# arm.net
KiCad netlist of a schematic drawn in Altium Designer
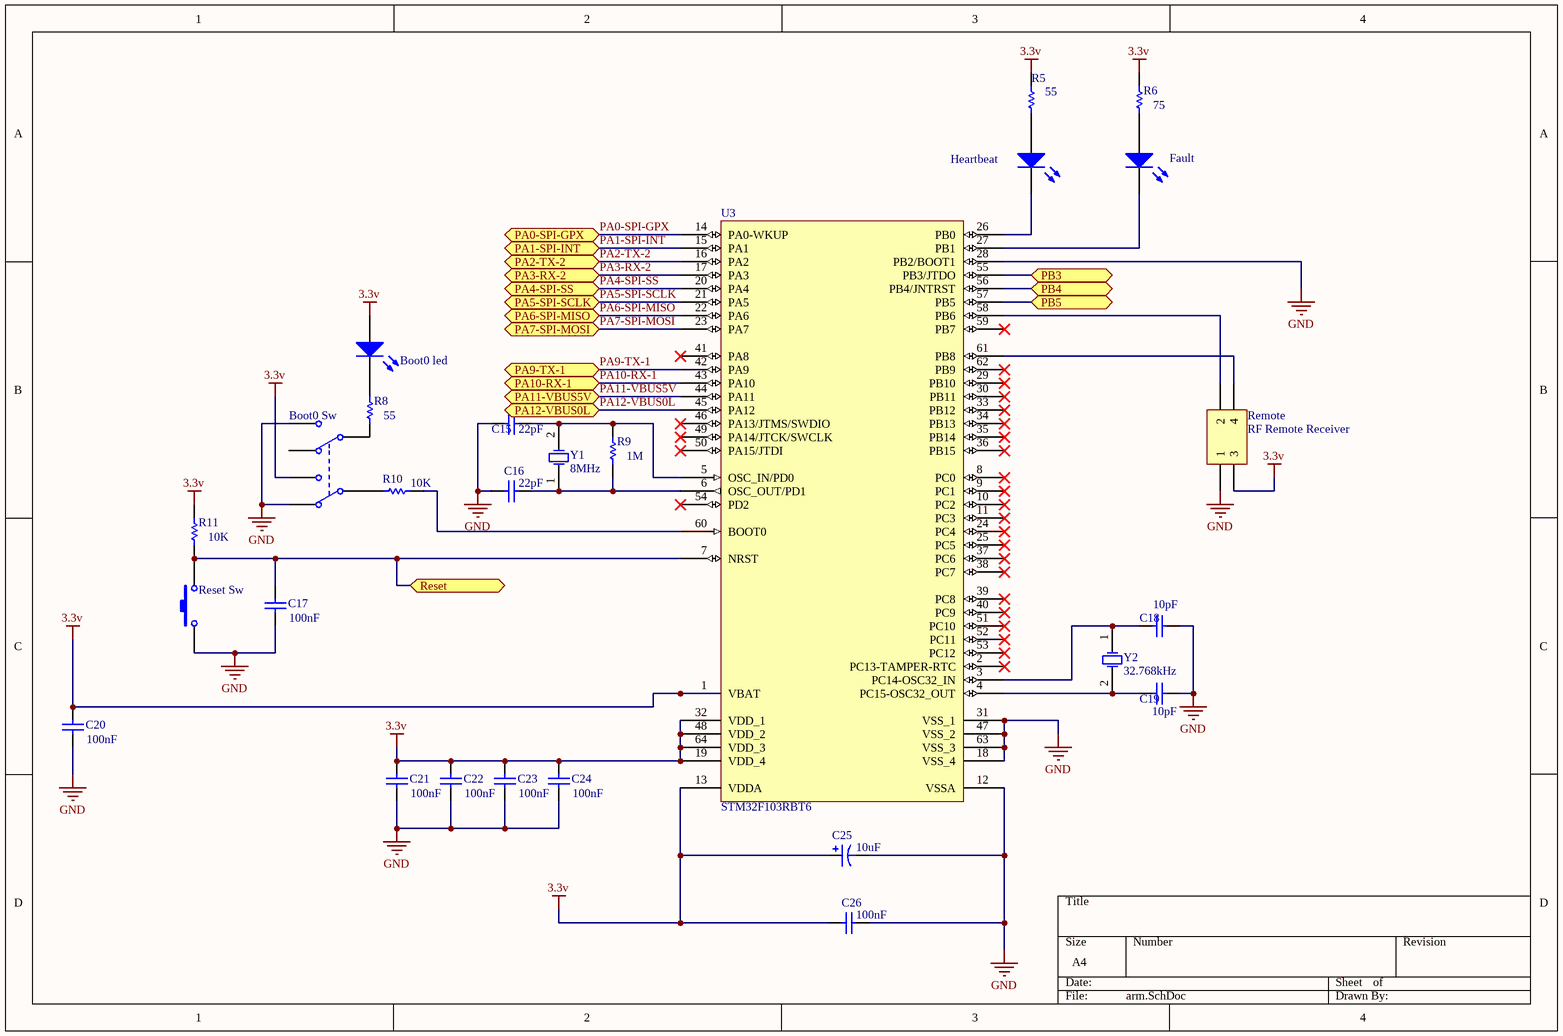
[diagram p0: arm.SchDoc]

(export (version "E")
  (design (tool "Eeschema 10.0.6"))
  (components
    (comp (ref "Boot0")
      (value "Boot0 led")
      (footprint "3.2X1.6X1.1")
      (description "Typical RED, GREEN, YELLOW, AMBER GaAs LED")
      (fields (field (name "PUBLISHER") "Altium Limited"))
      (libsource (lib "Miscellaneous Devices") (part "LED2"))
    )
    (comp (ref "Boot0 Sw")
      (value "BOOT0 SW")
      (footprint "Switch DPDT")
      (description "Switch")
      (fields (field (name "PUBLISHER") "Altium Limited"))
      (libsource (lib "Miscellaneous Devices") (part "SW DPDT"))
    )
    (comp (ref "C15")
      (value "22pF")
      (footprint "CAPC1608L")
      (description "Capacitor")
      (fields (field (name "Comment") "Cap") (field (name "PUBLISHER") "Altium Limited"))
      (libsource (lib "Miscellaneous Devices") (part "Cap"))
    )
    (comp (ref "C16")
      (value "22pF")
      (footprint "CAPC1608L")
      (description "Capacitor")
      (fields (field (name "Comment") "Cap") (field (name "PUBLISHER") "Altium Limited"))
      (libsource (lib "Miscellaneous Devices") (part "Cap"))
    )
    (comp (ref "C17")
      (value "100nF")
      (footprint "CAPC1608L")
      (description "Capacitor")
      (fields (field (name "Comment") "Cap") (field (name "PUBLISHER") "Altium Limited"))
      (libsource (lib "Miscellaneous Devices") (part "Cap"))
    )
    (comp (ref "C18")
      (value "10pF")
      (footprint "CAPC1608L")
      (description "Capacitor")
      (fields (field (name "Comment") "Cap") (field (name "PUBLISHER") "Altium Limited"))
      (libsource (lib "Miscellaneous Devices") (part "Cap"))
    )
    (comp (ref "C19")
      (value "10pF")
      (footprint "CAPC1608L")
      (description "Capacitor")
      (fields (field (name "Comment") "Cap") (field (name "PUBLISHER") "Altium Limited"))
      (libsource (lib "Miscellaneous Devices") (part "Cap"))
    )
    (comp (ref "C20")
      (value "100nF")
      (footprint "CAPC1608L")
      (description "Capacitor")
      (fields (field (name "Comment") "Cap") (field (name "PUBLISHER") "Altium Limited"))
      (libsource (lib "Miscellaneous Devices") (part "Cap"))
    )
    (comp (ref "C21")
      (value "100nF")
      (footprint "CAPC1608L")
      (description "Capacitor")
      (fields (field (name "Comment") "Cap") (field (name "PUBLISHER") "Altium Limited"))
      (libsource (lib "Miscellaneous Devices") (part "Cap"))
    )
    (comp (ref "C22")
      (value "100nF")
      (footprint "CAPC1608L")
      (description "Capacitor")
      (fields (field (name "Comment") "Cap") (field (name "PUBLISHER") "Altium Limited"))
      (libsource (lib "Miscellaneous Devices") (part "Cap"))
    )
    (comp (ref "C23")
      (value "100nF")
      (footprint "CAPC1608L")
      (description "Capacitor")
      (fields (field (name "Comment") "Cap") (field (name "PUBLISHER") "Altium Limited"))
      (libsource (lib "Miscellaneous Devices") (part "Cap"))
    )
    (comp (ref "C24")
      (value "100nF")
      (footprint "CAPC1608L")
      (description "Capacitor")
      (fields (field (name "Comment") "Cap") (field (name "PUBLISHER") "Altium Limited"))
      (libsource (lib "Miscellaneous Devices") (part "Cap"))
    )
    (comp (ref "C25")
      (value "10uF")
      (footprint "CAPC3216M")
      (description "Polarized Capacitor (Surface Mount)")
      (fields (field (name "Comment") "Cap Pol3") (field (name "PUBLISHER") "Altium Limited"))
      (libsource (lib "Miscellaneous Devices") (part "Cap Pol3"))
    )
    (comp (ref "C26")
      (value "100nF")
      (footprint "CAPC1608L")
      (description "Capacitor")
      (fields (field (name "Comment") "Cap") (field (name "PUBLISHER") "Altium Limited"))
      (libsource (lib "Miscellaneous Devices") (part "Cap"))
    )
    (comp (ref "Fault")
      (value "Fault LED")
      (footprint "3.2X1.6X1.1")
      (description "Typical RED, GREEN, YELLOW, AMBER GaAs LED")
      (fields (field (name "PUBLISHER") "Altium Limited"))
      (libsource (lib "Miscellaneous Devices") (part "LED2"))
    )
    (comp (ref "Heartbeat")
      (value "Heartbeat LED")
      (footprint "3.2X1.6X1.1")
      (description "Typical RED, GREEN, YELLOW, AMBER GaAs LED")
      (fields (field (name "PUBLISHER") "Altium Limited"))
      (libsource (lib "Miscellaneous Devices") (part "LED2"))
    )
    (comp (ref "R5")
      (value "55")
      (footprint "RESC1608L")
      (description "Resistor")
      (fields (field (name "Comment") "Res1") (field (name "PUBLISHER") "Altium Limited"))
      (libsource (lib "Miscellaneous Devices") (part "Res1"))
    )
    (comp (ref "R6")
      (value "75")
      (footprint "RESC1608L")
      (description "Resistor")
      (fields (field (name "Comment") "Res1") (field (name "PUBLISHER") "Altium Limited"))
      (libsource (lib "Miscellaneous Devices") (part "Res1"))
    )
    (comp (ref "R8")
      (value "55")
      (footprint "RESC1608L")
      (description "Resistor")
      (fields (field (name "Comment") "Res1") (field (name "PUBLISHER") "Altium Limited"))
      (libsource (lib "Miscellaneous Devices") (part "Res1"))
    )
    (comp (ref "R9")
      (value "1M")
      (footprint "RESC1608L")
      (description "Resistor")
      (fields (field (name "Comment") "Res1") (field (name "PUBLISHER") "Altium Limited"))
      (libsource (lib "Miscellaneous Devices") (part "Res1"))
    )
    (comp (ref "R10")
      (value "10K")
      (footprint "RESC1608L")
      (description "Resistor")
      (fields (field (name "Comment") "Res1") (field (name "PUBLISHER") "Altium Limited"))
      (libsource (lib "Miscellaneous Devices") (part "Res1"))
    )
    (comp (ref "R11")
      (value "10K")
      (footprint "RESC1608L")
      (description "Resistor")
      (fields (field (name "Comment") "Res1") (field (name "PUBLISHER") "Altium Limited"))
      (libsource (lib "Miscellaneous Devices") (part "Res1"))
    )
    (comp (ref "Remote")
      (value "RF Remote Receiver")
      (footprint "NES connector")
      (description "Header, 2-Pin, Dual row")
      (fields (field (name "PUBLISHER") "Altium Limited"))
      (libsource (lib "Miscellaneous Connectors") (part "Header 2X2"))
    )
    (comp (ref "Reset Sw")
      (value "RESET SW")
      (footprint "tackSwitch")
      (description "Switch")
      (fields (field (name "PUBLISHER") "Altium Limited"))
      (libsource (lib "Miscellaneous Devices") (part "SW-PB"))
    )
    (comp (ref "U3")
      (value "STM32F103RBT6")
      (footprint "LQFP64_N")
      (description "STM32 ARM-based 32-bit MCU with 128 Kbytes Flash, 64-pin LQFP, Industrial Temperature")
      (fields (field (name "PUBLISHER") "Altium Limited"))
      (libsource (lib "ST Microcontroller 32-Bit STM32") (part "STM32F103RBT6"))
    )
    (comp (ref "Y1")
      (value "8MHz")
      (footprint "HC-49U")
      (description "Crystal Oscillator")
      (fields (field (name "PUBLISHER") "Altium Limited"))
      (libsource (lib "Miscellaneous Devices") (part "XTAL"))
    )
    (comp (ref "Y2")
      (value "32.768kHz")
      (footprint "R26")
      (description "Crystal Oscillator")
      (fields (field (name "PUBLISHER") "Altium Limited"))
      (libsource (lib "Miscellaneous Devices") (part "XTAL"))
    )
  )
  (nets
    (net (code "1") (name "/PA0-SPI-GPX") (class "Default")
      (node (ref "U3") (pin "14") (pinfunction "PA0-WKUP_14") (pintype "bidirectional"))
    )
    (net (code "2") (name "/PA1-SPI-INT") (class "Default")
      (node (ref "U3") (pin "15") (pinfunction "PA1_15") (pintype "bidirectional"))
    )
    (net (code "3") (name "/PA2-TX-2") (class "Default")
      (node (ref "U3") (pin "16") (pinfunction "PA2_16") (pintype "bidirectional"))
    )
    (net (code "4") (name "/PA3-RX-2") (class "Default")
      (node (ref "U3") (pin "17") (pinfunction "PA3_17") (pintype "bidirectional"))
    )
    (net (code "5") (name "/PA4-SPI-SS") (class "Default")
      (node (ref "U3") (pin "20") (pinfunction "PA4_20") (pintype "bidirectional"))
    )
    (net (code "6") (name "/PA5-SPI-SCLK") (class "Default")
      (node (ref "U3") (pin "21") (pinfunction "PA5_21") (pintype "bidirectional"))
    )
    (net (code "7") (name "/PA6-SPI-MISO") (class "Default")
      (node (ref "U3") (pin "22") (pinfunction "PA6_22") (pintype "bidirectional"))
    )
    (net (code "8") (name "/PA7-SPI-MOSI") (class "Default")
      (node (ref "U3") (pin "23") (pinfunction "PA7_23") (pintype "bidirectional"))
    )
    (net (code "9") (name "/PA9-TX-1") (class "Default")
      (node (ref "U3") (pin "42") (pinfunction "PA9_42") (pintype "bidirectional"))
    )
    (net (code "10") (name "/PA10-RX-1") (class "Default")
      (node (ref "U3") (pin "43") (pinfunction "PA10_43") (pintype "bidirectional"))
    )
    (net (code "11") (name "/PA11-VBUS5V") (class "Default")
      (node (ref "U3") (pin "44") (pinfunction "PA11_44") (pintype "bidirectional"))
    )
    (net (code "12") (name "/PA12-VBUS0L") (class "Default")
      (node (ref "U3") (pin "45") (pinfunction "PA12_45") (pintype "bidirectional"))
    )
    (net (code "13") (name "/PB3") (class "Default")
      (node (ref "U3") (pin "55") (pinfunction "PB3/JTDO_55") (pintype "bidirectional"))
    )
    (net (code "14") (name "/PB4") (class "Default")
      (node (ref "U3") (pin "56") (pinfunction "PB4/JNTRST_56") (pintype "bidirectional"))
    )
    (net (code "15") (name "/PB5") (class "Default")
      (node (ref "U3") (pin "57") (pinfunction "PB5_57") (pintype "bidirectional"))
    )
    (net (code "16") (name "/Reset") (class "Default")
      (node (ref "C17") (pin "2") (pinfunction "2_2") (pintype "passive"))
      (node (ref "R11") (pin "1") (pinfunction "1_1") (pintype "passive"))
      (node (ref "Reset Sw") (pin "2") (pinfunction "2_2") (pintype "passive"))
      (node (ref "U3") (pin "7") (pinfunction "NRST_7") (pintype "bidirectional"))
    )
    (net (code "17") (name "3.3v") (class "Default")
      (node (ref "Boot0") (pin "1") (pinfunction "A_1") (pintype "passive"))
      (node (ref "Boot0 Sw") (pin "2") (pinfunction "NO1_2") (pintype "passive"))
      (node (ref "C20") (pin "2") (pinfunction "2_2") (pintype "passive"))
      (node (ref "C21") (pin "2") (pinfunction "2_2") (pintype "passive"))
      (node (ref "C22") (pin "2") (pinfunction "2_2") (pintype "passive"))
      (node (ref "C23") (pin "2") (pinfunction "2_2") (pintype "passive"))
      (node (ref "C24") (pin "2") (pinfunction "2_2") (pintype "passive"))
      (node (ref "C25") (pin "1") (pinfunction "1_1") (pintype "passive"))
      (node (ref "C26") (pin "1") (pinfunction "1_1") (pintype "passive"))
      (node (ref "R11") (pin "2") (pinfunction "2_2") (pintype "passive"))
      (node (ref "R5") (pin "2") (pinfunction "2_2") (pintype "passive"))
      (node (ref "R6") (pin "2") (pinfunction "2_2") (pintype "passive"))
      (node (ref "Remote") (pin "3") (pinfunction "3_3") (pintype "passive"))
      (node (ref "U3") (pin "1") (pinfunction "VBAT_1") (pintype "power_in"))
      (node (ref "U3") (pin "13") (pinfunction "VDDA_13") (pintype "power_in"))
      (node (ref "U3") (pin "19") (pinfunction "VDD_4_19") (pintype "power_in"))
      (node (ref "U3") (pin "32") (pinfunction "VDD_1_32") (pintype "power_in"))
      (node (ref "U3") (pin "48") (pinfunction "VDD_2_48") (pintype "power_in"))
      (node (ref "U3") (pin "64") (pinfunction "VDD_3_64") (pintype "power_in"))
    )
    (net (code "18") (name "GND") (class "Default")
      (node (ref "Boot0 Sw") (pin "1") (pinfunction "NC1_1") (pintype "passive"))
      (node (ref "Boot0 Sw") (pin "6") (pinfunction "NO2_6") (pintype "passive"))
      (node (ref "C15") (pin "1") (pinfunction "1_1") (pintype "passive"))
      (node (ref "C16") (pin "1") (pinfunction "1_1") (pintype "passive"))
      (node (ref "C17") (pin "1") (pinfunction "1_1") (pintype "passive"))
      (node (ref "C18") (pin "1") (pinfunction "1_1") (pintype "passive"))
      (node (ref "C19") (pin "1") (pinfunction "1_1") (pintype "passive"))
      (node (ref "C20") (pin "1") (pinfunction "1_1") (pintype "passive"))
      (node (ref "C21") (pin "1") (pinfunction "1_1") (pintype "passive"))
      (node (ref "C22") (pin "1") (pinfunction "1_1") (pintype "passive"))
      (node (ref "C23") (pin "1") (pinfunction "1_1") (pintype "passive"))
      (node (ref "C24") (pin "1") (pinfunction "1_1") (pintype "passive"))
      (node (ref "C25") (pin "2") (pinfunction "2_2") (pintype "passive"))
      (node (ref "C26") (pin "2") (pinfunction "2_2") (pintype "passive"))
      (node (ref "Remote") (pin "1") (pinfunction "1_1") (pintype "passive"))
      (node (ref "Reset Sw") (pin "1") (pinfunction "1_1") (pintype "passive"))
      (node (ref "U3") (pin "12") (pinfunction "VSSA_12") (pintype "power_in"))
      (node (ref "U3") (pin "18") (pinfunction "VSS_4_18") (pintype "power_in"))
      (node (ref "U3") (pin "28") (pinfunction "PB2/BOOT1_28") (pintype "bidirectional"))
      (node (ref "U3") (pin "31") (pinfunction "VSS_1_31") (pintype "power_in"))
      (node (ref "U3") (pin "47") (pinfunction "VSS_2_47") (pintype "power_in"))
      (node (ref "U3") (pin "63") (pinfunction "VSS_3_63") (pintype "power_in"))
    )
    (net (code "19") (name "Net-(Boot0 Sw-COMMON1)") (class "Default")
      (node (ref "Boot0 Sw") (pin "3") (pinfunction "COMMON1_3") (pintype "passive"))
      (node (ref "R10") (pin "1") (pinfunction "1_1") (pintype "passive"))
    )
    (net (code "20") (name "Net-(Boot0 Sw-COMMON2)") (class "Default")
      (node (ref "Boot0 Sw") (pin "4") (pinfunction "COMMON2_4") (pintype "passive"))
      (node (ref "R8") (pin "1") (pinfunction "1_1") (pintype "passive"))
    )
    (net (code "21") (name "Net-(Boot0-K)") (class "Default")
      (node (ref "Boot0") (pin "2") (pinfunction "K_2") (pintype "passive"))
      (node (ref "R8") (pin "2") (pinfunction "2_2") (pintype "passive"))
    )
    (net (code "22") (name "Net-(Fault-A)") (class "Default")
      (node (ref "Fault") (pin "1") (pinfunction "A_1") (pintype "passive"))
      (node (ref "R6") (pin "1") (pinfunction "1_1") (pintype "passive"))
    )
    (net (code "23") (name "Net-(Fault-K)") (class "Default")
      (node (ref "Fault") (pin "2") (pinfunction "K_2") (pintype "passive"))
      (node (ref "U3") (pin "27") (pinfunction "PB1_27") (pintype "bidirectional"))
    )
    (net (code "24") (name "Net-(Heartbeat-A)") (class "Default")
      (node (ref "Heartbeat") (pin "1") (pinfunction "A_1") (pintype "passive"))
      (node (ref "R5") (pin "1") (pinfunction "1_1") (pintype "passive"))
    )
    (net (code "25") (name "Net-(Heartbeat-K)") (class "Default")
      (node (ref "Heartbeat") (pin "2") (pinfunction "K_2") (pintype "passive"))
      (node (ref "U3") (pin "26") (pinfunction "PB0_26") (pintype "bidirectional"))
    )
    (net (code "26") (name "Net-(U3-BOOT0)") (class "Default")
      (node (ref "R10") (pin "2") (pinfunction "2_2") (pintype "passive"))
      (node (ref "U3") (pin "60") (pinfunction "BOOT0_60") (pintype "input"))
    )
    (net (code "27") (name "Net-(U3-OSC_IN{slash}PD0)") (class "Default")
      (node (ref "C15") (pin "2") (pinfunction "2_2") (pintype "passive"))
      (node (ref "R9") (pin "1") (pinfunction "1_1") (pintype "passive"))
      (node (ref "U3") (pin "5") (pinfunction "OSC_IN/PD0_5") (pintype "input"))
      (node (ref "Y1") (pin "2") (pinfunction "OSC2_2") (pintype "passive"))
    )
    (net (code "28") (name "Net-(U3-OSC_OUT{slash}PD1)") (class "Default")
      (node (ref "C16") (pin "2") (pinfunction "2_2") (pintype "passive"))
      (node (ref "R9") (pin "2") (pinfunction "2_2") (pintype "passive"))
      (node (ref "U3") (pin "6") (pinfunction "OSC_OUT/PD1_6") (pintype "output"))
      (node (ref "Y1") (pin "1") (pinfunction "OSC1_1") (pintype "passive"))
    )
    (net (code "29") (name "Net-(U3-PB6)") (class "Default")
      (node (ref "Remote") (pin "2") (pinfunction "2_2") (pintype "passive"))
      (node (ref "U3") (pin "58") (pinfunction "PB6_58") (pintype "bidirectional"))
    )
    (net (code "30") (name "Net-(U3-PB8)") (class "Default")
      (node (ref "Remote") (pin "4") (pinfunction "4_4") (pintype "passive"))
      (node (ref "U3") (pin "61") (pinfunction "PB8_61") (pintype "bidirectional"))
    )
    (net (code "31") (name "Net-(U3-PC14-OSC32_IN)") (class "Default")
      (node (ref "C18") (pin "2") (pinfunction "2_2") (pintype "passive"))
      (node (ref "U3") (pin "3") (pinfunction "PC14-OSC32_IN_3") (pintype "bidirectional"))
      (node (ref "Y2") (pin "1") (pinfunction "OSC1_1") (pintype "passive"))
    )
    (net (code "32") (name "Net-(U3-PC15-OSC32_OUT)") (class "Default")
      (node (ref "C19") (pin "2") (pinfunction "2_2") (pintype "passive"))
      (node (ref "U3") (pin "4") (pinfunction "PC15-OSC32_OUT_4") (pintype "bidirectional"))
      (node (ref "Y2") (pin "2") (pinfunction "OSC2_2") (pintype "passive"))
    )
    (net (code "33") (name "unconnected-(Boot0 Sw-NC2-Pad5)") (class "Default")
      (node (ref "Boot0 Sw") (pin "5") (pinfunction "NC2_5") (pintype "passive"))
    )
    (net (code "34") (name "unconnected-(U3-PA8-Pad41)") (class "Default")
      (node (ref "U3") (pin "41") (pinfunction "PA8_41") (pintype "bidirectional+no_connect"))
    )
    (net (code "35") (name "unconnected-(U3-PA13{slash}JTMS{slash}SWDIO-Pad46)") (class "Default")
      (node (ref "U3") (pin "46") (pinfunction "PA13/JTMS/SWDIO_46") (pintype "bidirectional+no_connect"))
    )
    (net (code "36") (name "unconnected-(U3-PA14{slash}JTCK{slash}SWCLK-Pad49)") (class "Default")
      (node (ref "U3") (pin "49") (pinfunction "PA14/JTCK/SWCLK_49") (pintype "bidirectional+no_connect"))
    )
    (net (code "37") (name "unconnected-(U3-PA15{slash}JTDI-Pad50)") (class "Default")
      (node (ref "U3") (pin "50") (pinfunction "PA15/JTDI_50") (pintype "bidirectional+no_connect"))
    )
    (net (code "38") (name "unconnected-(U3-PB7-Pad59)") (class "Default")
      (node (ref "U3") (pin "59") (pinfunction "PB7_59") (pintype "bidirectional+no_connect"))
    )
    (net (code "39") (name "unconnected-(U3-PB9-Pad62)") (class "Default")
      (node (ref "U3") (pin "62") (pinfunction "PB9_62") (pintype "bidirectional+no_connect"))
    )
    (net (code "40") (name "unconnected-(U3-PB10-Pad29)") (class "Default")
      (node (ref "U3") (pin "29") (pinfunction "PB10_29") (pintype "bidirectional+no_connect"))
    )
    (net (code "41") (name "unconnected-(U3-PB11-Pad30)") (class "Default")
      (node (ref "U3") (pin "30") (pinfunction "PB11_30") (pintype "bidirectional+no_connect"))
    )
    (net (code "42") (name "unconnected-(U3-PB12-Pad33)") (class "Default")
      (node (ref "U3") (pin "33") (pinfunction "PB12_33") (pintype "bidirectional+no_connect"))
    )
    (net (code "43") (name "unconnected-(U3-PB13-Pad34)") (class "Default")
      (node (ref "U3") (pin "34") (pinfunction "PB13_34") (pintype "bidirectional+no_connect"))
    )
    (net (code "44") (name "unconnected-(U3-PB14-Pad35)") (class "Default")
      (node (ref "U3") (pin "35") (pinfunction "PB14_35") (pintype "bidirectional+no_connect"))
    )
    (net (code "45") (name "unconnected-(U3-PB15-Pad36)") (class "Default")
      (node (ref "U3") (pin "36") (pinfunction "PB15_36") (pintype "bidirectional+no_connect"))
    )
    (net (code "46") (name "unconnected-(U3-PC0-Pad8)") (class "Default")
      (node (ref "U3") (pin "8") (pinfunction "PC0_8") (pintype "bidirectional+no_connect"))
    )
    (net (code "47") (name "unconnected-(U3-PC1-Pad9)") (class "Default")
      (node (ref "U3") (pin "9") (pinfunction "PC1_9") (pintype "bidirectional+no_connect"))
    )
    (net (code "48") (name "unconnected-(U3-PC2-Pad10)") (class "Default")
      (node (ref "U3") (pin "10") (pinfunction "PC2_10") (pintype "bidirectional+no_connect"))
    )
    (net (code "49") (name "unconnected-(U3-PC3-Pad11)") (class "Default")
      (node (ref "U3") (pin "11") (pinfunction "PC3_11") (pintype "bidirectional+no_connect"))
    )
    (net (code "50") (name "unconnected-(U3-PC4-Pad24)") (class "Default")
      (node (ref "U3") (pin "24") (pinfunction "PC4_24") (pintype "bidirectional+no_connect"))
    )
    (net (code "51") (name "unconnected-(U3-PC5-Pad25)") (class "Default")
      (node (ref "U3") (pin "25") (pinfunction "PC5_25") (pintype "bidirectional+no_connect"))
    )
    (net (code "52") (name "unconnected-(U3-PC6-Pad37)") (class "Default")
      (node (ref "U3") (pin "37") (pinfunction "PC6_37") (pintype "bidirectional+no_connect"))
    )
    (net (code "53") (name "unconnected-(U3-PC7-Pad38)") (class "Default")
      (node (ref "U3") (pin "38") (pinfunction "PC7_38") (pintype "bidirectional+no_connect"))
    )
    (net (code "54") (name "unconnected-(U3-PC8-Pad39)") (class "Default")
      (node (ref "U3") (pin "39") (pinfunction "PC8_39") (pintype "bidirectional+no_connect"))
    )
    (net (code "55") (name "unconnected-(U3-PC9-Pad40)") (class "Default")
      (node (ref "U3") (pin "40") (pinfunction "PC9_40") (pintype "bidirectional+no_connect"))
    )
    (net (code "56") (name "unconnected-(U3-PC10-Pad51)") (class "Default")
      (node (ref "U3") (pin "51") (pinfunction "PC10_51") (pintype "bidirectional+no_connect"))
    )
    (net (code "57") (name "unconnected-(U3-PC11-Pad52)") (class "Default")
      (node (ref "U3") (pin "52") (pinfunction "PC11_52") (pintype "bidirectional+no_connect"))
    )
    (net (code "58") (name "unconnected-(U3-PC12-Pad53)") (class "Default")
      (node (ref "U3") (pin "53") (pinfunction "PC12_53") (pintype "bidirectional+no_connect"))
    )
    (net (code "59") (name "unconnected-(U3-PC13-TAMPER-RTC-Pad2)") (class "Default")
      (node (ref "U3") (pin "2") (pinfunction "PC13-TAMPER-RTC_2") (pintype "bidirectional+no_connect"))
    )
    (net (code "60") (name "unconnected-(U3-PD2-Pad54)") (class "Default")
      (node (ref "U3") (pin "54") (pinfunction "PD2_54") (pintype "bidirectional+no_connect"))
    )
  )
)
